# terms.net
KiCad netlist of a schematic drawn in Altium Designer
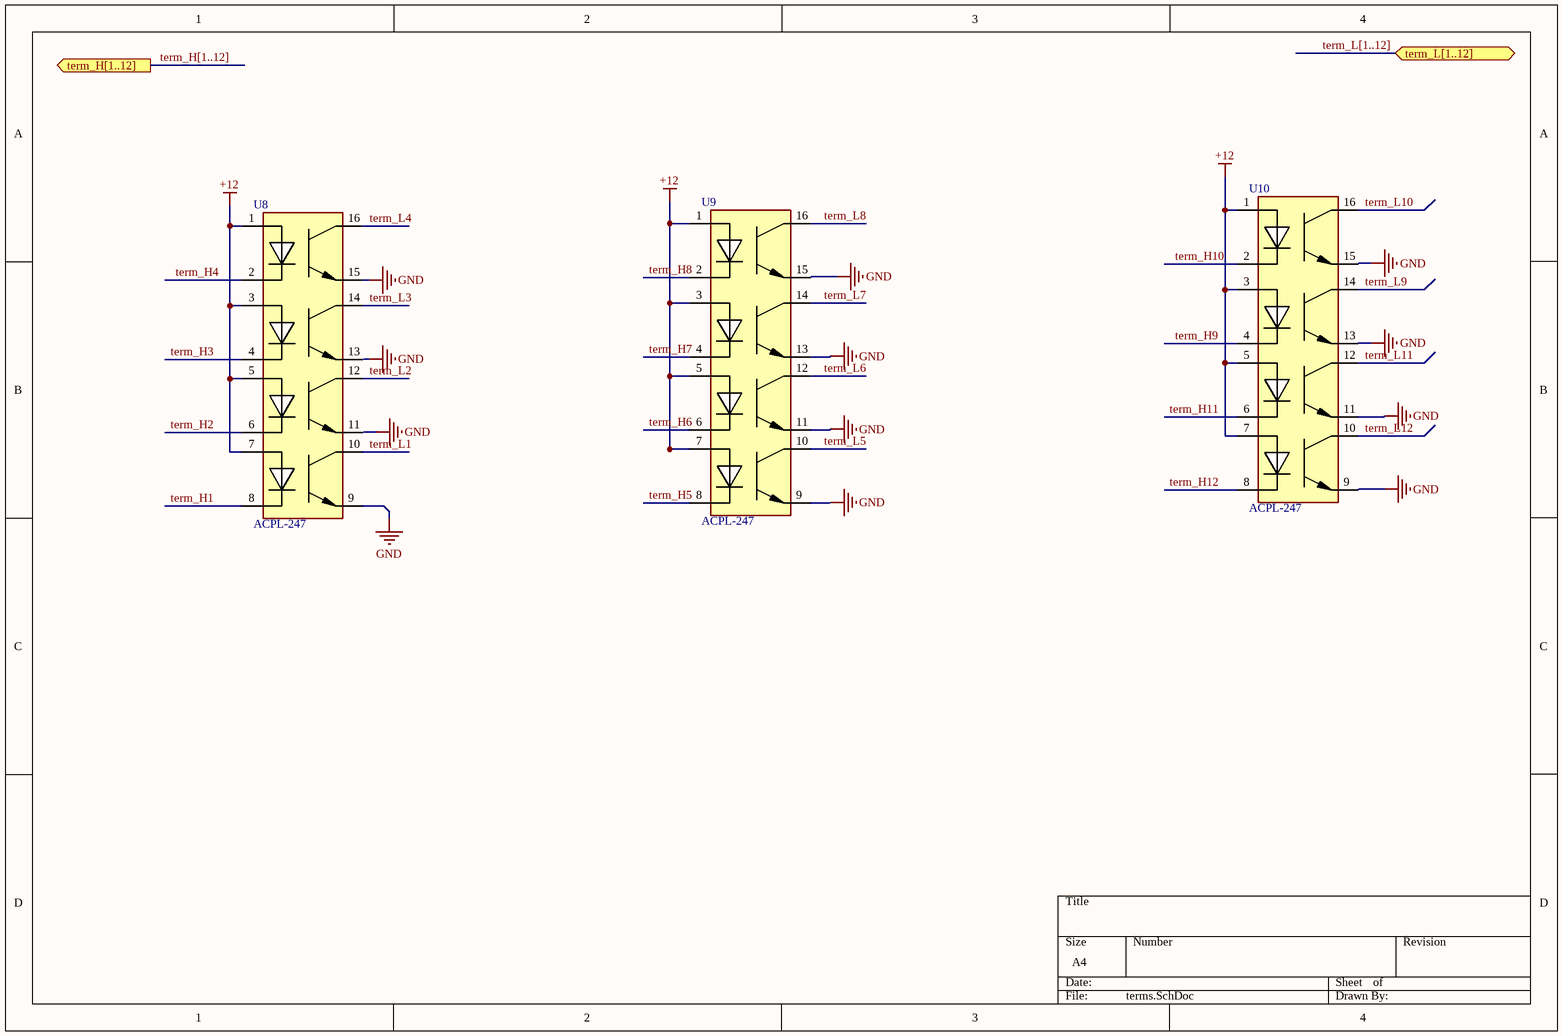
[diagram p0: terms.SchDoc]

(export (version "E")
  (design (tool "Eeschema 10.0.6"))
  (components
    (comp (ref "U8")
      (value "ACPL-247")
      (footprint "SOIC127P600-16M")
      (description "DC Input Multi-Channel Half-Pitch  Phototransistor Optocoupler")
      (libsource (lib "Schlib1") (part "ACPL-247"))
    )
    (comp (ref "U9")
      (value "ACPL-247")
      (footprint "SOIC127P600-16M")
      (description "DC Input Multi-Channel Half-Pitch  Phototransistor Optocoupler")
      (libsource (lib "Schlib1") (part "ACPL-247"))
    )
    (comp (ref "U10")
      (value "ACPL-247")
      (footprint "SOIC127P600-16M")
      (description "DC Input Multi-Channel Half-Pitch  Phototransistor Optocoupler")
      (libsource (lib "Schlib1") (part "ACPL-247"))
    )
  )
  (nets
    (net (code "1") (name "+12") (class "Default")
      (node (ref "U10") (pin "1") (pinfunction "1_1") (pintype "passive"))
      (node (ref "U10") (pin "3") (pinfunction "3_3") (pintype "passive"))
      (node (ref "U10") (pin "5") (pinfunction "5_5") (pintype "passive"))
      (node (ref "U10") (pin "7") (pinfunction "7_7") (pintype "passive"))
      (node (ref "U8") (pin "1") (pinfunction "1_1") (pintype "passive"))
      (node (ref "U8") (pin "3") (pinfunction "3_3") (pintype "passive"))
      (node (ref "U8") (pin "5") (pinfunction "5_5") (pintype "passive"))
      (node (ref "U8") (pin "7") (pinfunction "7_7") (pintype "passive"))
      (node (ref "U9") (pin "1") (pinfunction "1_1") (pintype "passive"))
      (node (ref "U9") (pin "3") (pinfunction "3_3") (pintype "passive"))
      (node (ref "U9") (pin "5") (pinfunction "5_5") (pintype "passive"))
      (node (ref "U9") (pin "7") (pinfunction "7_7") (pintype "passive"))
    )
    (net (code "2") (name "/term_H1") (class "Default")
      (node (ref "U8") (pin "8") (pinfunction "8_8") (pintype "passive"))
    )
    (net (code "3") (name "/term_H2") (class "Default")
      (node (ref "U8") (pin "6") (pinfunction "6_6") (pintype "passive"))
    )
    (net (code "4") (name "/term_H3") (class "Default")
      (node (ref "U8") (pin "4") (pinfunction "4_4") (pintype "passive"))
    )
    (net (code "5") (name "/term_H4") (class "Default")
      (node (ref "U8") (pin "2") (pinfunction "2_2") (pintype "passive"))
    )
    (net (code "6") (name "/term_H5") (class "Default")
      (node (ref "U9") (pin "8") (pinfunction "8_8") (pintype "passive"))
    )
    (net (code "7") (name "/term_H6") (class "Default")
      (node (ref "U9") (pin "6") (pinfunction "6_6") (pintype "passive"))
    )
    (net (code "8") (name "/term_H7") (class "Default")
      (node (ref "U9") (pin "4") (pinfunction "4_4") (pintype "passive"))
    )
    (net (code "9") (name "/term_H8") (class "Default")
      (node (ref "U9") (pin "2") (pinfunction "2_2") (pintype "passive"))
    )
    (net (code "10") (name "/term_H9") (class "Default")
      (node (ref "U10") (pin "4") (pinfunction "4_4") (pintype "passive"))
    )
    (net (code "11") (name "/term_H10") (class "Default")
      (node (ref "U10") (pin "2") (pinfunction "2_2") (pintype "passive"))
    )
    (net (code "12") (name "/term_H11") (class "Default")
      (node (ref "U10") (pin "6") (pinfunction "6_6") (pintype "passive"))
    )
    (net (code "13") (name "/term_H12") (class "Default")
      (node (ref "U10") (pin "8") (pinfunction "8_8") (pintype "passive"))
    )
    (net (code "15") (name "/term_L1") (class "Default")
      (node (ref "U8") (pin "10") (pinfunction "10_10") (pintype "passive"))
    )
    (net (code "16") (name "/term_L2") (class "Default")
      (node (ref "U8") (pin "12") (pinfunction "12_12") (pintype "passive"))
    )
    (net (code "17") (name "/term_L3") (class "Default")
      (node (ref "U8") (pin "14") (pinfunction "14_14") (pintype "passive"))
    )
    (net (code "18") (name "/term_L4") (class "Default")
      (node (ref "U8") (pin "16") (pinfunction "16_16") (pintype "passive"))
    )
    (net (code "19") (name "/term_L5") (class "Default")
      (node (ref "U9") (pin "10") (pinfunction "10_10") (pintype "passive"))
    )
    (net (code "20") (name "/term_L6") (class "Default")
      (node (ref "U9") (pin "12") (pinfunction "12_12") (pintype "passive"))
    )
    (net (code "21") (name "/term_L7") (class "Default")
      (node (ref "U9") (pin "14") (pinfunction "14_14") (pintype "passive"))
    )
    (net (code "22") (name "/term_L8") (class "Default")
      (node (ref "U9") (pin "16") (pinfunction "16_16") (pintype "passive"))
    )
    (net (code "23") (name "/term_L9") (class "Default")
      (node (ref "U10") (pin "14") (pinfunction "14_14") (pintype "passive"))
    )
    (net (code "24") (name "/term_L10") (class "Default")
      (node (ref "U10") (pin "16") (pinfunction "16_16") (pintype "passive"))
    )
    (net (code "25") (name "/term_L11") (class "Default")
      (node (ref "U10") (pin "12") (pinfunction "12_12") (pintype "passive"))
    )
    (net (code "26") (name "/term_L12") (class "Default")
      (node (ref "U10") (pin "10") (pinfunction "10_10") (pintype "passive"))
    )
    (net (code "28") (name "GND") (class "Default")
      (node (ref "U10") (pin "11") (pinfunction "11_11") (pintype "passive"))
      (node (ref "U10") (pin "15") (pinfunction "15_15") (pintype "passive"))
      (node (ref "U10") (pin "9") (pinfunction "9_9") (pintype "passive"))
      (node (ref "U8") (pin "11") (pinfunction "11_11") (pintype "passive"))
      (node (ref "U8") (pin "13") (pinfunction "13_13") (pintype "passive"))
      (node (ref "U8") (pin "15") (pinfunction "15_15") (pintype "passive"))
      (node (ref "U8") (pin "9") (pinfunction "9_9") (pintype "passive"))
      (node (ref "U9") (pin "11") (pinfunction "11_11") (pintype "passive"))
      (node (ref "U9") (pin "13") (pinfunction "13_13") (pintype "passive"))
      (node (ref "U9") (pin "15") (pinfunction "15_15") (pintype "passive"))
      (node (ref "U9") (pin "9") (pinfunction "9_9") (pintype "passive"))
    )
    (net (code "29") (name "unconnected-(U10-Pad13)") (class "Default")
      (node (ref "U10") (pin "13") (pinfunction "13_13") (pintype "passive"))
    )
  )
)
